# Power_Management.net
KiCad netlist of a schematic drawn in Altium Designer
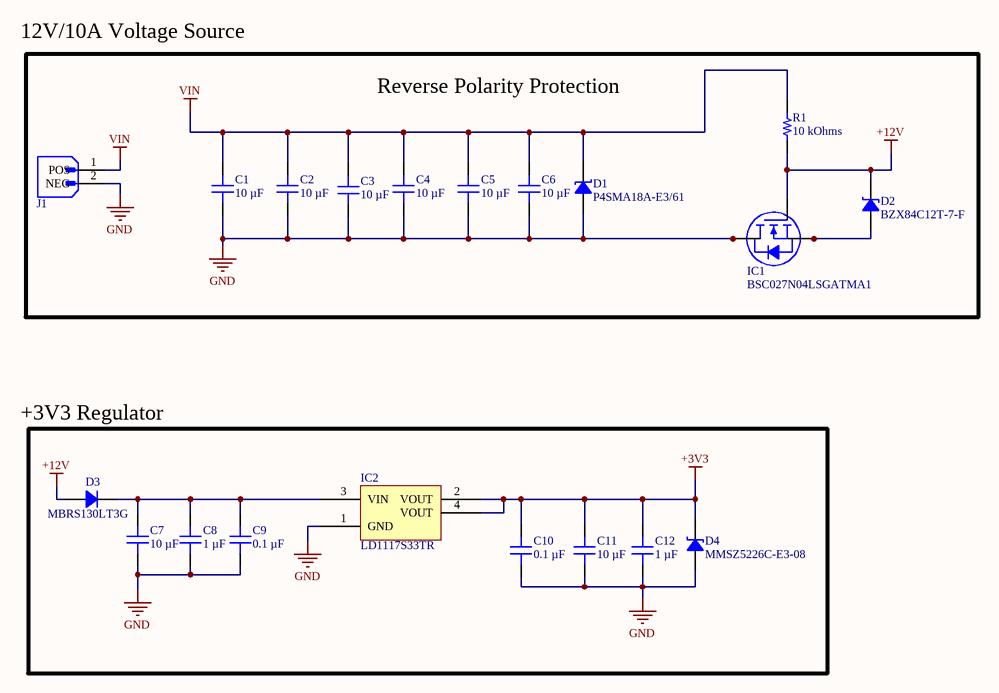
[diagram p0: Power Management.SchDoc]

(export (version "E")
  (design (tool "Eeschema 10.0.6"))
  (components
    (comp (ref "C1")
      (value "10 µF")
      (footprint "MURATA CAP GRM31M 1206_3216")
      (description "CAP CER 10UF 25V X5R 1206")
      (fields
        (field (name "PART NUMBER") "GRM319R61E106MA12D")
        (field (name "CAPACITANCE") "10 µF")
        (field (name "MANUFACTURER") "Murata Electronics")
      )
      (libsource (lib "Celestial Altium Library - altium_library") (part "Capacitor"))
    )
    (comp (ref "C2")
      (value "10 µF")
      (footprint "MURATA CAP GRM31M 1206_3216")
      (description "CAP CER 10UF 25V X5R 1206")
      (fields
        (field (name "PART NUMBER") "GRM319R61E106MA12D")
        (field (name "CAPACITANCE") "10 µF")
        (field (name "MANUFACTURER") "Murata Electronics")
      )
      (libsource (lib "Celestial Altium Library - altium_library") (part "Capacitor"))
    )
    (comp (ref "C3")
      (value "10 µF")
      (footprint "MURATA CAP GRM31M 1206_3216")
      (description "CAP CER 10UF 25V X5R 1206")
      (fields
        (field (name "PART NUMBER") "GRM319R61E106MA12D")
        (field (name "CAPACITANCE") "10 µF")
        (field (name "MANUFACTURER") "Murata Electronics")
      )
      (libsource (lib "Celestial Altium Library - altium_library") (part "Capacitor"))
    )
    (comp (ref "C4")
      (value "10 µF")
      (footprint "MURATA CAP GRM31M 1206_3216")
      (description "CAP CER 10UF 25V X5R 1206")
      (fields
        (field (name "PART NUMBER") "GRM319R61E106MA12D")
        (field (name "CAPACITANCE") "10 µF")
        (field (name "MANUFACTURER") "Murata Electronics")
      )
      (libsource (lib "Celestial Altium Library - altium_library") (part "Capacitor"))
    )
    (comp (ref "C5")
      (value "10 µF")
      (footprint "MURATA CAP GRM31M 1206_3216")
      (description "CAP CER 10UF 25V X5R 1206")
      (fields
        (field (name "PART NUMBER") "GRM319R61E106MA12D")
        (field (name "CAPACITANCE") "10 µF")
        (field (name "MANUFACTURER") "Murata Electronics")
      )
      (libsource (lib "Celestial Altium Library - altium_library") (part "Capacitor"))
    )
    (comp (ref "C6")
      (value "10 µF")
      (footprint "MURATA CAP GRM31M 1206_3216")
      (description "CAP CER 10UF 25V X5R 1206")
      (fields
        (field (name "PART NUMBER") "GRM319R61E106MA12D")
        (field (name "CAPACITANCE") "10 µF")
        (field (name "MANUFACTURER") "Murata Electronics")
      )
      (libsource (lib "Celestial Altium Library - altium_library") (part "Capacitor"))
    )
    (comp (ref "C7")
      (value "10 µF")
      (footprint "CAP 0603_1608")
      (description "CAP CER 10UF 16V X5R 0603")
      (fields
        (field (name "PART NUMBER") "CC0603MRX5R7BB106")
        (field (name "CAPACITANCE") "10 µF")
        (field (name "MANUFACTURER") "Yageo")
      )
      (libsource (lib "Celestial Altium Library - altium_library") (part "Capacitor"))
    )
    (comp (ref "C8")
      (value "1 µF")
      (footprint "MURATA GCM188 0603_1608")
      (description "CAP CER 1UF 16V X7R 0603")
      (fields
        (field (name "PART NUMBER") "GCM188R71C105KA64J")
        (field (name "CAPACITANCE") "1 µF")
        (field (name "MANUFACTURER") "Murata Electronics")
      )
      (libsource (lib "Celestial Altium Library - altium_library") (part "Capacitor"))
    )
    (comp (ref "C9")
      (value "0.1 µF")
      (footprint "CAP 0603_1608")
      (description "CAP CER 0.1UF 25V X7R 0603")
      (fields
        (field (name "PART NUMBER") "C0603X104M3RAC7867")
        (field (name "CAPACITANCE") "0.1 µF")
        (field (name "MANUFACTURER") "KEMET")
      )
      (libsource (lib "Celestial Altium Library - altium_library") (part "Capacitor"))
    )
    (comp (ref "C10")
      (value "0.1 µF")
      (footprint "CAP 0603_1608")
      (description "CAP CER 0.1UF 25V X7R 0603")
      (fields
        (field (name "PART NUMBER") "C0603X104M3RAC7867")
        (field (name "CAPACITANCE") "0.1 µF")
        (field (name "MANUFACTURER") "KEMET")
      )
      (libsource (lib "Celestial Altium Library - altium_library") (part "Capacitor"))
    )
    (comp (ref "C11")
      (value "10 µF")
      (footprint "CAP 0603_1608")
      (description "CAP CER 10UF 16V X5R 0603")
      (fields
        (field (name "PART NUMBER") "CC0603MRX5R7BB106")
        (field (name "CAPACITANCE") "10 µF")
        (field (name "MANUFACTURER") "Yageo")
      )
      (libsource (lib "Celestial Altium Library - altium_library") (part "Capacitor"))
    )
    (comp (ref "C12")
      (value "1 µF")
      (footprint "MURATA GCM188 0603_1608")
      (description "CAP CER 1UF 16V X7R 0603")
      (fields
        (field (name "PART NUMBER") "GCM188R71C105KA64J")
        (field (name "CAPACITANCE") "1 µF")
        (field (name "MANUFACTURER") "Murata Electronics")
      )
      (libsource (lib "Celestial Altium Library - altium_library") (part "Capacitor"))
    )
    (comp (ref "D1")
      (value "P4SMA18A-E3/61")
      (footprint "DO214AC SMA")
      (description "TVS DIODE 15.3V 25.2V DO214AC")
      (fields (field (name "MANUFACTURER") "Vishay Semiconductor Diodes Division"))
      (libsource (lib "Celestial Altium Library - altium_library") (part "DIODE TVS UNI"))
    )
    (comp (ref "D2")
      (value "BZX84C12T-7-F")
      (footprint "DIODES SOT-523")
      (description "DIODE ZENER 12V 150MW SOT523")
      (fields (field (name "MANUFACTURER") "Diodes Incorporated") (field (name "TOLERANCE") "±5%"))
      (libsource (lib "Celestial Altium Library - altium_library") (part "Diode Zener"))
    )
    (comp (ref "D3")
      (value "MBRS130LT3G")
      (footprint "DO214AA SMB")
      (description "DIODE SCHOTTKY 30V 2A SMB")
      (fields (field (name "MANUFACTURER") "ON Semiconductor"))
      (libsource (lib "Celestial Altium Library - altium_library") (part "Diode"))
    )
    (comp (ref "D4")
      (value "MMSZ5226C-E3-08")
      (footprint "SOD-123")
      (description "DIODE ZENER 3.3V 500MW SOD123")
      (fields
        (field (name "MANUFACTURER") "Vishay Semiconductor Diodes Division")
        (field (name "TOLERANCE") "±2%")
      )
      (libsource (lib "Celestial Altium Library - altium_library") (part "Diode Zener"))
    )
    (comp (ref "IC1")
      (value "BSC027N04LSGATMA1")
      (footprint "INFINEON PG-TDSON-8 6.15X5.32MM")
      (description "MOSFET N-CH 40V 24A/100A TDSON")
      (fields (field (name "MANUFACTURER") "Infineon Technologies"))
      (libsource (lib "Celestial Altium Library - altium_library") (part "INFINEON BSC MOSFET N-CH"))
    )
    (comp (ref "IC2")
      (value "LD1117S33TR")
      (footprint "ST SOT-223")
      (description "IC REG LINEAR 3.3V 800MA SOT223")
      (fields (field (name "MANUFACTURER") "STMicroelectronics"))
      (libsource (lib "Celestial Altium Library - altium_library") (part "ST LD1117"))
    )
    (comp (ref "J1")
      (value "XT90 Connector")
      (footprint "XT90 Conn")
      (description "Li-Po battery connector")
      (libsource (lib "PCB_Lib") (part "XT90 Connector"))
    )
    (comp (ref "R1")
      (value "10 kOhms")
      (footprint "YAGEO RES 0603_1608")
      (description "RES SMD 10K OHM 1% 1/10W 0603")
      (fields (field (name "PART NUMBER") "AA0603FR-0710KL") (field (name "MANUFACTURER") "Yageo"))
      (libsource (lib "Celestial Altium Library - altium_library") (part "Resistor"))
    )
  )
  (nets
    (net (code "1") (name "+3V3") (class "Default")
      (node (ref "C10") (pin "2") (pinfunction "2_2") (pintype "passive"))
      (node (ref "C11") (pin "2") (pinfunction "2_2") (pintype "passive"))
      (node (ref "C12") (pin "2") (pinfunction "2_2") (pintype "passive"))
      (node (ref "D4") (pin "2") (pinfunction "2_2") (pintype "passive"))
      (node (ref "IC2") (pin "2") (pinfunction "VOUT_2") (pintype "passive"))
      (node (ref "IC2") (pin "4") (pinfunction "VOUT_4") (pintype "passive"))
    )
    (net (code "2") (name "+12V") (class "Default")
      (node (ref "D2") (pin "2") (pinfunction "2_2") (pintype "passive"))
      (node (ref "D3") (pin "1") (pinfunction "1_1") (pintype "passive"))
      (node (ref "IC1") (pin "4") (pinfunction "G_4") (pintype "passive"))
      (node (ref "R1") (pin "1") (pinfunction "1_1") (pintype "passive"))
    )
    (net (code "3") (name "GND") (class "Default")
      (node (ref "C1") (pin "1") (pinfunction "1_1") (pintype "passive"))
      (node (ref "C10") (pin "1") (pinfunction "1_1") (pintype "passive"))
      (node (ref "C11") (pin "1") (pinfunction "1_1") (pintype "passive"))
      (node (ref "C12") (pin "1") (pinfunction "1_1") (pintype "passive"))
      (node (ref "C2") (pin "1") (pinfunction "1_1") (pintype "passive"))
      (node (ref "C3") (pin "1") (pinfunction "1_1") (pintype "passive"))
      (node (ref "C4") (pin "1") (pinfunction "1_1") (pintype "passive"))
      (node (ref "C5") (pin "1") (pinfunction "1_1") (pintype "passive"))
      (node (ref "C6") (pin "1") (pinfunction "1_1") (pintype "passive"))
      (node (ref "C7") (pin "1") (pinfunction "1_1") (pintype "passive"))
      (node (ref "C8") (pin "1") (pinfunction "1_1") (pintype "passive"))
      (node (ref "C9") (pin "1") (pinfunction "1_1") (pintype "passive"))
      (node (ref "D1") (pin "1") (pinfunction "1_1") (pintype "passive"))
      (node (ref "D4") (pin "1") (pinfunction "1_1") (pintype "passive"))
      (node (ref "IC1") (pin "5") (pinfunction "D_5") (pintype "passive"))
      (node (ref "IC1") (pin "6") (pinfunction "D_6") (pintype "passive"))
      (node (ref "IC1") (pin "7") (pinfunction "D_7") (pintype "passive"))
      (node (ref "IC1") (pin "8") (pinfunction "D_8") (pintype "passive"))
      (node (ref "IC2") (pin "1") (pinfunction "GND_1") (pintype "passive"))
      (node (ref "J1") (pin "2") (pinfunction "NEG_2") (pintype "passive"))
    )
    (net (code "4") (name "Net-(D2-Pad1)") (class "Default")
      (node (ref "D2") (pin "1") (pinfunction "1_1") (pintype "passive"))
      (node (ref "IC1") (pin "1") (pinfunction "S_1") (pintype "passive"))
      (node (ref "IC1") (pin "2") (pinfunction "S_2") (pintype "passive"))
      (node (ref "IC1") (pin "3") (pinfunction "S_3") (pintype "passive"))
    )
    (net (code "5") (name "Net-(IC2-VIN)") (class "Default")
      (node (ref "C7") (pin "2") (pinfunction "2_2") (pintype "passive"))
      (node (ref "C8") (pin "2") (pinfunction "2_2") (pintype "passive"))
      (node (ref "C9") (pin "2") (pinfunction "2_2") (pintype "passive"))
      (node (ref "D3") (pin "2") (pinfunction "2_2") (pintype "passive"))
      (node (ref "IC2") (pin "3") (pinfunction "VIN_3") (pintype "passive"))
    )
    (net (code "6") (name "VIN") (class "Default")
      (node (ref "C1") (pin "2") (pinfunction "2_2") (pintype "passive"))
      (node (ref "C2") (pin "2") (pinfunction "2_2") (pintype "passive"))
      (node (ref "C3") (pin "2") (pinfunction "2_2") (pintype "passive"))
      (node (ref "C4") (pin "2") (pinfunction "2_2") (pintype "passive"))
      (node (ref "C5") (pin "2") (pinfunction "2_2") (pintype "passive"))
      (node (ref "C6") (pin "2") (pinfunction "2_2") (pintype "passive"))
      (node (ref "D1") (pin "2") (pinfunction "2_2") (pintype "passive"))
      (node (ref "J1") (pin "1") (pinfunction "POS_1") (pintype "passive"))
      (node (ref "R1") (pin "2") (pinfunction "2_2") (pintype "passive"))
    )
  )
)
